# A1356.net
KiCad netlist of a schematic drawn in Altium Designer
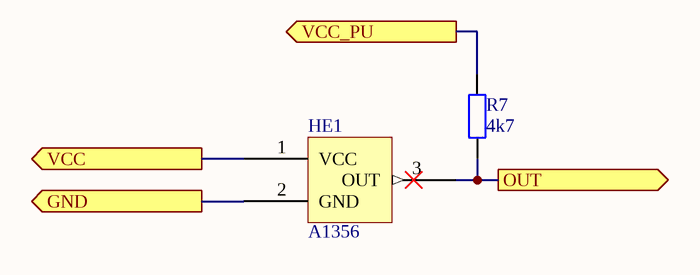
[diagram p0: A1356.SchDoc]

(export (version "E")
  (design (tool "Eeschema 10.0.6"))
  (components
    (comp (ref "HE1")
      (value "A1356")
      (footprint "3-Pin SIP")
      (description "Linear Hall-Effect Sensor")
      (libsource (lib "bitbots") (part "A1356"))
    )
    (comp (ref "R7")
      (value "4k7")
      (footprint "R2012")
      (description "Resistor")
      (fields (field (name "PUBLISHER") "Altium Limited"))
      (libsource (lib "Miscellaneous Devices") (part "Res2"))
    )
  )
  (nets
    (net (code "1") (name "/GND") (class "Default")
      (node (ref "HE1") (pin "2") (pinfunction "GND_2") (pintype "power_in"))
    )
    (net (code "2") (name "/OUT") (class "Default")
      (node (ref "HE1") (pin "3") (pinfunction "OUT_3") (pintype "output"))
      (node (ref "R7") (pin "1") (pinfunction "1_1") (pintype "passive"))
    )
    (net (code "3") (name "/VCC") (class "Default")
      (node (ref "HE1") (pin "1") (pinfunction "VCC_1") (pintype "power_in"))
    )
    (net (code "4") (name "/VCC_PU") (class "Default")
      (node (ref "R7") (pin "2") (pinfunction "2_2") (pintype "passive"))
    )
  )
)
